# MasterControlChip.net
KiCad netlist of a schematic drawn in Altium Designer
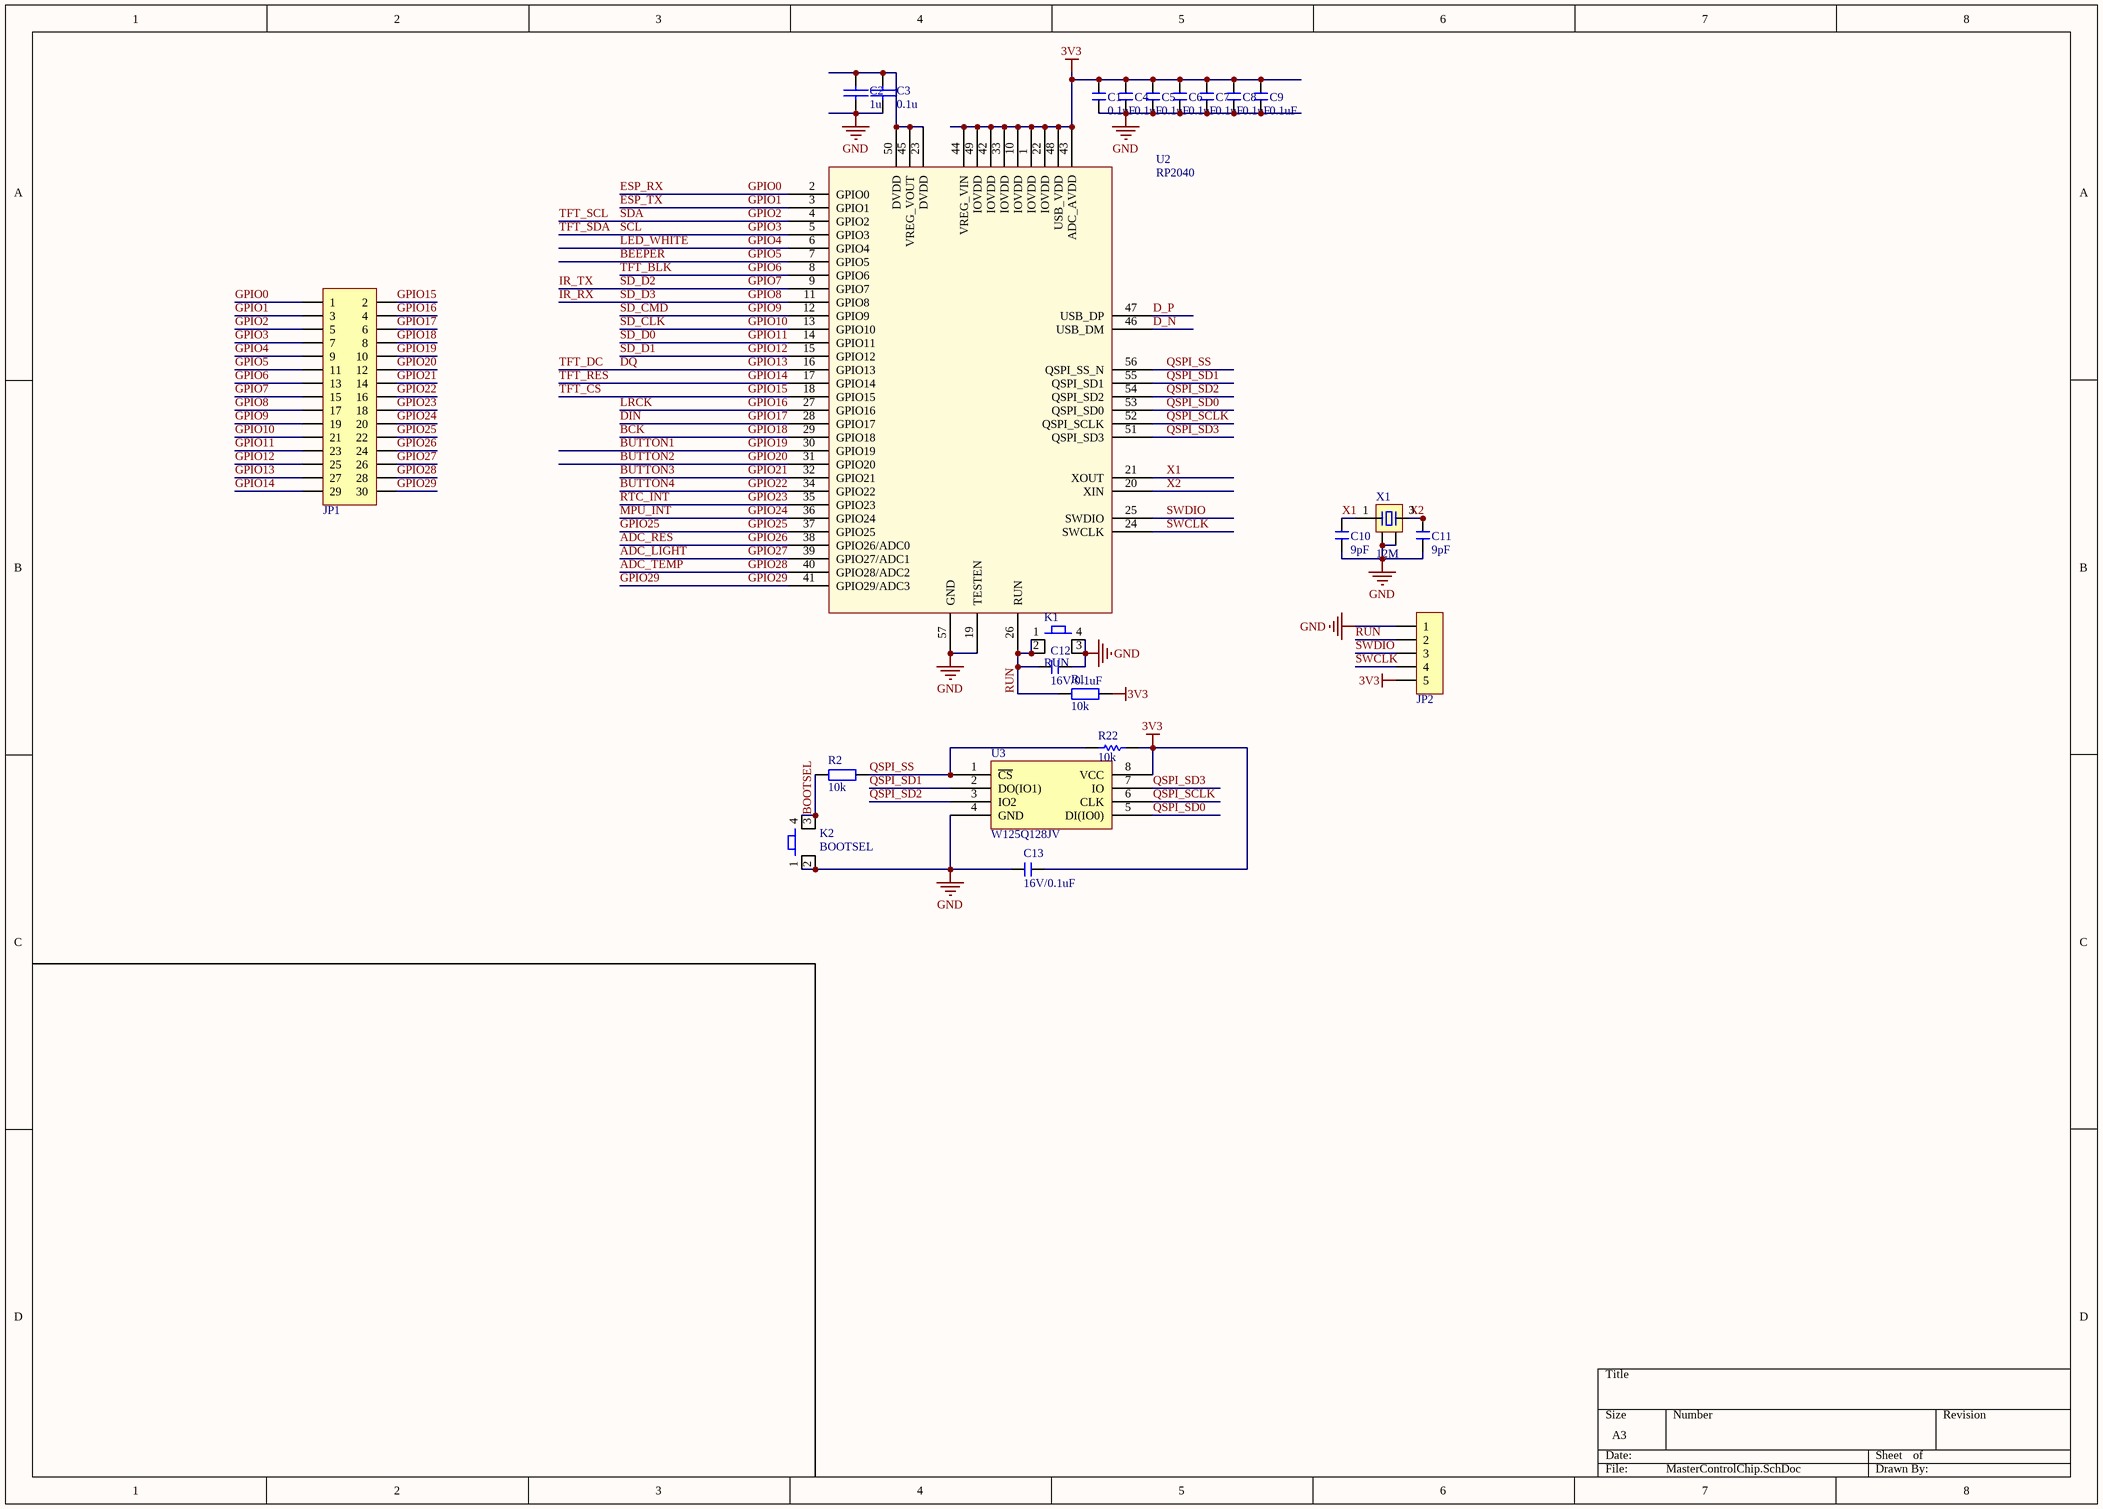
[diagram p0: MasterControlChip.SchDoc]

(export (version "E")
  (design (tool "Eeschema 10.0.6"))
  (components
    (comp (ref "C1")
      (value "0.1uF")
      (footprint "C 0603_L")
      (description "无极性贴片电容")
      (fields (field (name "版权归属") "源创客"))
      (libsource (lib "3.1   - 电阻-电容-电感") (part "C"))
    )
    (comp (ref "C2")
      (value "1u")
      (footprint "C 0603_L")
      (description "靠近RP2040")
      (libsource (lib "电容") (part "CAP"))
    )
    (comp (ref "C3")
      (value "0.1u")
      (footprint "C 0603_L")
      (description "无极性电容")
      (libsource (lib "电容") (part "CAP"))
    )
    (comp (ref "C4")
      (value "0.1uF")
      (footprint "C 0603_L")
      (description "无极性贴片电容")
      (fields (field (name "版权归属") "源创客"))
      (libsource (lib "3.1   - 电阻-电容-电感") (part "C"))
    )
    (comp (ref "C5")
      (value "0.1uF")
      (footprint "C 0603_L")
      (description "无极性贴片电容")
      (fields (field (name "版权归属") "源创客"))
      (libsource (lib "3.1   - 电阻-电容-电感") (part "C"))
    )
    (comp (ref "C6")
      (value "0.1uF")
      (footprint "C 0603_L")
      (description "无极性贴片电容")
      (fields (field (name "版权归属") "源创客"))
      (libsource (lib "3.1   - 电阻-电容-电感") (part "C"))
    )
    (comp (ref "C7")
      (value "0.1uF")
      (footprint "C 0603_L")
      (description "无极性贴片电容")
      (fields (field (name "版权归属") "源创客"))
      (libsource (lib "3.1   - 电阻-电容-电感") (part "C"))
    )
    (comp (ref "C8")
      (value "0.1uF")
      (footprint "C 0603_L")
      (description "无极性贴片电容")
      (fields (field (name "版权归属") "源创客"))
      (libsource (lib "3.1   - 电阻-电容-电感") (part "C"))
    )
    (comp (ref "C9")
      (value "0.1uF")
      (footprint "C 0603_L")
      (description "无极性贴片电容")
      (fields (field (name "版权归属") "源创客"))
      (libsource (lib "3.1   - 电阻-电容-电感") (part "C"))
    )
    (comp (ref "C10")
      (value "9pF")
      (footprint "C 0603_L")
      (description "无极性贴片电容")
      (fields (field (name "版权归属") "源创客"))
      (libsource (lib "3.1   - 电阻-电容-电感") (part "C"))
    )
    (comp (ref "C11")
      (value "9pF")
      (footprint "C 0603_L")
      (description "无极性贴片电容")
      (fields (field (name "版权归属") "源创客"))
      (libsource (lib "3.1   - 电阻-电容-电感") (part "C"))
    )
    (comp (ref "C12")
      (value "16V/0.1uF")
      (footprint "C 0603_L")
      (description "无极性贴片电容")
      (fields (field (name "版权归属") "源创客"))
      (libsource (lib "3.1   - 电阻-电容-电感") (part "C"))
    )
    (comp (ref "C13")
      (value "16V/0.1uF")
      (footprint "C 0603_L")
      (description "无极性贴片电容")
      (fields (field (name "版权归属") "源创客"))
      (libsource (lib "3.1   - 电阻-电容-电感") (part "C"))
    )
    (comp (ref "JP1")
      (value "Header 2X11")
      (footprint "HDR2.54-LI-2x15P")
      (description "15*2P接插件")
      (fields (field (name "版权归属") "源创客"))
      (libsource (lib "4.6   - 接插件-脚距2.54") (part "Header 15X2"))
    )
    (comp (ref "JP2")
      (value "HDR-1X5")
      (footprint "HDR2.54-M-LI-5P")
      (description "5P接插件")
      (fields (field (name "版权归属") "源创客"))
      (libsource (lib "4.6   - 接插件-脚距2.54") (part "Header 5"))
    )
    (comp (ref "K1") (value "RUN") (footprint "四角贴片开关") (libsource (lib "Schlib1") (part "四角轻触开关")))
    (comp (ref "K2") (value "BOOTSEL") (footprint "四角贴片开关") (libsource (lib "Schlib1") (part "四角轻触开关")))
    (comp (ref "R1")
      (value "10k")
      (footprint "R 0603_L")
      (description "贴片电阻")
      (fields (field (name "版权归属") "源创客"))
      (libsource (lib "3.1   - 电阻-电容-电感") (part "R"))
    )
    (comp (ref "R2")
      (value "10k")
      (footprint "R 0603_L")
      (description "贴片电阻")
      (fields (field (name "版权归属") "源创客"))
      (libsource (lib "3.1   - 电阻-电容-电感") (part "R"))
    )
    (comp (ref "R22") (value "10k") (footprint "0603R") (libsource (lib "电阻") (part "RES")))
    (comp (ref "U2") (value "RP2040") (footprint "QFN-56") (libsource (lib "Schlib1") (part "RP2040")))
    (comp (ref "U3")
      (value "W125Q128JV")
      (footprint "SOIC-8-208mil")
      (libsource (lib "Schlib1") (part "W125Q128JV"))
    )
    (comp (ref "X1")
      (value "12M")
      (footprint "OSC 3225-4P")
      (description "4脚无源晶振")
      (libsource (lib "晶振") (part "XTAL-4P"))
    )
  )
  (nets
    (net (code "1") (name "/ADC_LIGHT") (class "Default")
      (node (ref "JP1") (pin "26") (pinfunction "26_26") (pintype "passive"))
      (node (ref "U2") (pin "39") (pinfunction "GPIO27/ADC1_39") (pintype "passive"))
    )
    (net (code "2") (name "/ADC_RES") (class "Default")
      (node (ref "JP1") (pin "24") (pinfunction "24_24") (pintype "passive"))
      (node (ref "U2") (pin "38") (pinfunction "GPIO26/ADC0_38") (pintype "passive"))
    )
    (net (code "3") (name "/ADC_TEMP") (class "Default")
      (node (ref "JP1") (pin "28") (pinfunction "28_28") (pintype "passive"))
      (node (ref "U2") (pin "40") (pinfunction "GPIO28/ADC2_40") (pintype "passive"))
    )
    (net (code "4") (name "/BCK") (class "Default")
      (node (ref "JP1") (pin "8") (pinfunction "8_8") (pintype "passive"))
      (node (ref "U2") (pin "29") (pinfunction "GPIO18_29") (pintype "passive"))
    )
    (net (code "5") (name "/BEEPER") (class "Default")
      (node (ref "JP1") (pin "11") (pinfunction "11_11") (pintype "passive"))
      (node (ref "U2") (pin "7") (pinfunction "GPIO5_7") (pintype "passive"))
    )
    (net (code "6") (name "/BOOTSEL") (class "Default")
      (node (ref "K2") (pin "3") (pinfunction "4_3") (pintype "passive"))
      (node (ref "K2") (pin "4") (pinfunction "5_4") (pintype "passive"))
      (node (ref "R2") (pin "2") (pinfunction "2_2") (pintype "passive"))
    )
    (net (code "7") (name "/BUTTON1") (class "Default")
      (node (ref "JP1") (pin "10") (pinfunction "10_10") (pintype "passive"))
      (node (ref "U2") (pin "30") (pinfunction "GPIO19_30") (pintype "passive"))
    )
    (net (code "8") (name "/BUTTON2") (class "Default")
      (node (ref "JP1") (pin "12") (pinfunction "12_12") (pintype "passive"))
      (node (ref "U2") (pin "31") (pinfunction "GPIO20_31") (pintype "passive"))
    )
    (net (code "9") (name "/BUTTON3") (class "Default")
      (node (ref "JP1") (pin "14") (pinfunction "14_14") (pintype "passive"))
      (node (ref "U2") (pin "32") (pinfunction "GPIO21_32") (pintype "passive"))
    )
    (net (code "10") (name "/BUTTON4") (class "Default")
      (node (ref "JP1") (pin "16") (pinfunction "16_16") (pintype "passive"))
      (node (ref "U2") (pin "34") (pinfunction "GPIO22_34") (pintype "passive"))
    )
    (net (code "11") (name "/DIN") (class "Default")
      (node (ref "JP1") (pin "6") (pinfunction "6_6") (pintype "passive"))
      (node (ref "U2") (pin "28") (pinfunction "GPIO17_28") (pintype "passive"))
    )
    (net (code "12") (name "/DQ") (class "Default")
      (node (ref "JP1") (pin "27") (pinfunction "27_27") (pintype "passive"))
      (node (ref "U2") (pin "16") (pinfunction "GPIO13_16") (pintype "passive"))
    )
    (net (code "13") (name "/D_N") (class "Default")
      (node (ref "U2") (pin "46") (pinfunction "USB_DM_46") (pintype "passive"))
    )
    (net (code "14") (name "/D_P") (class "Default")
      (node (ref "U2") (pin "47") (pinfunction "USB_DP_47") (pintype "passive"))
    )
    (net (code "15") (name "/ESP_RX") (class "Default")
      (node (ref "JP1") (pin "1") (pinfunction "1_1") (pintype "passive"))
      (node (ref "U2") (pin "2") (pinfunction "GPIO0_2") (pintype "passive"))
    )
    (net (code "16") (name "/ESP_TX") (class "Default")
      (node (ref "JP1") (pin "3") (pinfunction "3_3") (pintype "passive"))
      (node (ref "U2") (pin "3") (pinfunction "GPIO1_3") (pintype "passive"))
    )
    (net (code "17") (name "/GPIO2") (class "Default")
      (node (ref "JP1") (pin "5") (pinfunction "5_5") (pintype "passive"))
      (node (ref "U2") (pin "4") (pinfunction "GPIO2_4") (pintype "passive"))
    )
    (net (code "18") (name "/GPIO3") (class "Default")
      (node (ref "JP1") (pin "7") (pinfunction "7_7") (pintype "passive"))
      (node (ref "U2") (pin "5") (pinfunction "GPIO3_5") (pintype "passive"))
    )
    (net (code "19") (name "/GPIO4") (class "Default")
      (node (ref "JP1") (pin "9") (pinfunction "9_9") (pintype "passive"))
      (node (ref "U2") (pin "6") (pinfunction "GPIO4_6") (pintype "passive"))
    )
    (net (code "20") (name "/GPIO6") (class "Default")
      (node (ref "JP1") (pin "13") (pinfunction "13_13") (pintype "passive"))
      (node (ref "U2") (pin "8") (pinfunction "GPIO6_8") (pintype "passive"))
    )
    (net (code "21") (name "/GPIO7") (class "Default")
      (node (ref "JP1") (pin "15") (pinfunction "15_15") (pintype "passive"))
      (node (ref "U2") (pin "9") (pinfunction "GPIO7_9") (pintype "passive"))
    )
    (net (code "22") (name "/GPIO8") (class "Default")
      (node (ref "JP1") (pin "17") (pinfunction "17_17") (pintype "passive"))
      (node (ref "U2") (pin "11") (pinfunction "GPIO8_11") (pintype "passive"))
    )
    (net (code "23") (name "/GPIO9") (class "Default")
      (node (ref "JP1") (pin "19") (pinfunction "19_19") (pintype "passive"))
      (node (ref "U2") (pin "12") (pinfunction "GPIO9_12") (pintype "passive"))
    )
    (net (code "24") (name "/GPIO10") (class "Default")
      (node (ref "JP1") (pin "21") (pinfunction "21_21") (pintype "passive"))
      (node (ref "U2") (pin "13") (pinfunction "GPIO10_13") (pintype "passive"))
    )
    (net (code "25") (name "/GPIO11") (class "Default")
      (node (ref "JP1") (pin "23") (pinfunction "23_23") (pintype "passive"))
      (node (ref "U2") (pin "14") (pinfunction "GPIO11_14") (pintype "passive"))
    )
    (net (code "26") (name "/GPIO12") (class "Default")
      (node (ref "JP1") (pin "25") (pinfunction "25_25") (pintype "passive"))
      (node (ref "U2") (pin "15") (pinfunction "GPIO12_15") (pintype "passive"))
    )
    (net (code "27") (name "/GPIO14") (class "Default")
      (node (ref "JP1") (pin "29") (pinfunction "29_29") (pintype "passive"))
      (node (ref "U2") (pin "17") (pinfunction "GPIO14_17") (pintype "passive"))
    )
    (net (code "28") (name "/GPIO15") (class "Default")
      (node (ref "JP1") (pin "2") (pinfunction "2_2") (pintype "passive"))
      (node (ref "U2") (pin "18") (pinfunction "GPIO15_18") (pintype "passive"))
    )
    (net (code "29") (name "/GPIO16") (class "Default")
      (node (ref "JP1") (pin "4") (pinfunction "4_4") (pintype "passive"))
      (node (ref "U2") (pin "27") (pinfunction "GPIO16_27") (pintype "passive"))
    )
    (net (code "30") (name "/GPIO23") (class "Default")
      (node (ref "JP1") (pin "18") (pinfunction "18_18") (pintype "passive"))
      (node (ref "U2") (pin "35") (pinfunction "GPIO23_35") (pintype "passive"))
    )
    (net (code "31") (name "/GPIO24") (class "Default")
      (node (ref "JP1") (pin "20") (pinfunction "20_20") (pintype "passive"))
      (node (ref "U2") (pin "36") (pinfunction "GPIO24_36") (pintype "passive"))
    )
    (net (code "32") (name "/GPIO25") (class "Default")
      (node (ref "JP1") (pin "22") (pinfunction "22_22") (pintype "passive"))
      (node (ref "U2") (pin "37") (pinfunction "GPIO25_37") (pintype "passive"))
    )
    (net (code "33") (name "/GPIO29") (class "Default")
      (node (ref "JP1") (pin "30") (pinfunction "30_30") (pintype "passive"))
      (node (ref "U2") (pin "41") (pinfunction "GPIO29/ADC3_41") (pintype "passive"))
    )
    (net (code "34") (name "/QSPI_SCLK") (class "Default")
      (node (ref "U2") (pin "52") (pinfunction "QSPI_SCLK_52") (pintype "passive"))
      (node (ref "U3") (pin "6") (pinfunction "CLK_6") (pintype "passive"))
    )
    (net (code "35") (name "/QSPI_SD0") (class "Default")
      (node (ref "U2") (pin "53") (pinfunction "QSPI_SD0_53") (pintype "passive"))
      (node (ref "U3") (pin "5") (pinfunction "DI(IO0)_5") (pintype "passive"))
    )
    (net (code "36") (name "/QSPI_SD1") (class "Default")
      (node (ref "U2") (pin "55") (pinfunction "QSPI_SD1_55") (pintype "passive"))
      (node (ref "U3") (pin "2") (pinfunction "DO(IO1)_2") (pintype "passive"))
    )
    (net (code "37") (name "/QSPI_SD2") (class "Default")
      (node (ref "U2") (pin "54") (pinfunction "QSPI_SD2_54") (pintype "passive"))
      (node (ref "U3") (pin "3") (pinfunction "IO2_3") (pintype "passive"))
    )
    (net (code "38") (name "/QSPI_SD3") (class "Default")
      (node (ref "U2") (pin "51") (pinfunction "QSPI_SD3_51") (pintype "passive"))
      (node (ref "U3") (pin "7") (pinfunction "IO_7") (pintype "passive"))
    )
    (net (code "39") (name "/QSPI_SS") (class "Default")
      (node (ref "R2") (pin "1") (pinfunction "1_1") (pintype "passive"))
      (node (ref "R22") (pin "1") (pinfunction "1_1") (pintype "passive"))
      (node (ref "U2") (pin "56") (pinfunction "QSPI_SS_N_56") (pintype "passive"))
      (node (ref "U3") (pin "1") (pinfunction "~{CS}_1") (pintype "passive"))
    )
    (net (code "40") (name "/RUN") (class "Default")
      (node (ref "C12") (pin "2") (pinfunction "2_2") (pintype "passive"))
      (node (ref "JP2") (pin "2") (pinfunction "2_2") (pintype "passive"))
      (node (ref "K1") (pin "1") (pinfunction "2_1") (pintype "passive"))
      (node (ref "K1") (pin "2") (pinfunction "3_2") (pintype "passive"))
      (node (ref "R1") (pin "2") (pinfunction "2_2") (pintype "passive"))
      (node (ref "U2") (pin "26") (pinfunction "RUN_26") (pintype "passive"))
    )
    (net (code "41") (name "/SWCLK") (class "Default")
      (node (ref "JP2") (pin "4") (pinfunction "4_4") (pintype "passive"))
      (node (ref "U2") (pin "24") (pinfunction "SWCLK_24") (pintype "passive"))
    )
    (net (code "42") (name "/SWDIO") (class "Default")
      (node (ref "JP2") (pin "3") (pinfunction "3_3") (pintype "passive"))
      (node (ref "U2") (pin "25") (pinfunction "SWDIO_25") (pintype "passive"))
    )
    (net (code "43") (name "/X1") (class "Default")
      (node (ref "C10") (pin "2") (pinfunction "2_2") (pintype "passive"))
      (node (ref "U2") (pin "21") (pinfunction "XOUT_21") (pintype "passive"))
      (node (ref "X1") (pin "1") (pinfunction "1_1") (pintype "passive"))
    )
    (net (code "44") (name "/X2") (class "Default")
      (node (ref "C11") (pin "2") (pinfunction "2_2") (pintype "passive"))
      (node (ref "U2") (pin "20") (pinfunction "XIN_20") (pintype "passive"))
      (node (ref "X1") (pin "3") (pinfunction "3_3") (pintype "passive"))
    )
    (net (code "45") (name "3V3") (class "Default")
      (node (ref "C1") (pin "2") (pinfunction "2_2") (pintype "passive"))
      (node (ref "C13") (pin "1") (pinfunction "1_1") (pintype "passive"))
      (node (ref "C4") (pin "2") (pinfunction "2_2") (pintype "passive"))
      (node (ref "C5") (pin "2") (pinfunction "2_2") (pintype "passive"))
      (node (ref "C6") (pin "2") (pinfunction "2_2") (pintype "passive"))
      (node (ref "C7") (pin "2") (pinfunction "2_2") (pintype "passive"))
      (node (ref "C8") (pin "2") (pinfunction "2_2") (pintype "passive"))
      (node (ref "C9") (pin "2") (pinfunction "2_2") (pintype "passive"))
      (node (ref "JP2") (pin "5") (pinfunction "5_5") (pintype "passive"))
      (node (ref "R1") (pin "1") (pinfunction "1_1") (pintype "passive"))
      (node (ref "R22") (pin "2") (pinfunction "2_2") (pintype "passive"))
      (node (ref "U2") (pin "1") (pinfunction "IOVDD_1") (pintype "passive"))
      (node (ref "U2") (pin "10") (pinfunction "IOVDD_10") (pintype "passive"))
      (node (ref "U2") (pin "22") (pinfunction "IOVDD_22") (pintype "passive"))
      (node (ref "U2") (pin "33") (pinfunction "IOVDD_33") (pintype "passive"))
      (node (ref "U2") (pin "42") (pinfunction "IOVDD_42") (pintype "passive"))
      (node (ref "U2") (pin "43") (pinfunction "ADC_AVDD_43") (pintype "passive"))
      (node (ref "U2") (pin "44") (pinfunction "VREG_VIN_44") (pintype "passive"))
      (node (ref "U2") (pin "48") (pinfunction "USB_VDD_48") (pintype "passive"))
      (node (ref "U2") (pin "49") (pinfunction "IOVDD_49") (pintype "passive"))
      (node (ref "U3") (pin "8") (pinfunction "VCC_8") (pintype "power_in"))
    )
    (net (code "46") (name "GND") (class "Default")
      (node (ref "C1") (pin "1") (pinfunction "1_1") (pintype "passive"))
      (node (ref "C10") (pin "1") (pinfunction "1_1") (pintype "passive"))
      (node (ref "C11") (pin "1") (pinfunction "1_1") (pintype "passive"))
      (node (ref "C12") (pin "1") (pinfunction "1_1") (pintype "passive"))
      (node (ref "C13") (pin "2") (pinfunction "2_2") (pintype "passive"))
      (node (ref "C2") (pin "1") (pinfunction "1_1") (pintype "passive"))
      (node (ref "C3") (pin "1") (pinfunction "1_1") (pintype "passive"))
      (node (ref "C4") (pin "1") (pinfunction "1_1") (pintype "passive"))
      (node (ref "C5") (pin "1") (pinfunction "1_1") (pintype "passive"))
      (node (ref "C6") (pin "1") (pinfunction "1_1") (pintype "passive"))
      (node (ref "C7") (pin "1") (pinfunction "1_1") (pintype "passive"))
      (node (ref "C8") (pin "1") (pinfunction "1_1") (pintype "passive"))
      (node (ref "C9") (pin "1") (pinfunction "1_1") (pintype "passive"))
      (node (ref "JP2") (pin "1") (pinfunction "1_1") (pintype "passive"))
      (node (ref "K1") (pin "3") (pinfunction "4_3") (pintype "passive"))
      (node (ref "K1") (pin "4") (pinfunction "5_4") (pintype "passive"))
      (node (ref "K2") (pin "1") (pinfunction "2_1") (pintype "passive"))
      (node (ref "K2") (pin "2") (pinfunction "3_2") (pintype "passive"))
      (node (ref "U2") (pin "19") (pinfunction "TESTEN_19") (pintype "passive"))
      (node (ref "U2") (pin "57") (pinfunction "GND_57") (pintype "passive"))
      (node (ref "U3") (pin "4") (pinfunction "GND_4") (pintype "power_in"))
      (node (ref "X1") (pin "2") (pinfunction "2_2") (pintype "passive"))
      (node (ref "X1") (pin "4") (pinfunction "4_4") (pintype "passive"))
    )
    (net (code "47") (name "Net-(U2-VREG_VOUT)") (class "Default")
      (node (ref "C2") (pin "2") (pinfunction "2_2") (pintype "passive"))
      (node (ref "C3") (pin "2") (pinfunction "2_2") (pintype "passive"))
      (node (ref "U2") (pin "23") (pinfunction "DVDD_23") (pintype "passive"))
      (node (ref "U2") (pin "45") (pinfunction "VREG_VOUT_45") (pintype "passive"))
      (node (ref "U2") (pin "50") (pinfunction "DVDD_50") (pintype "passive"))
    )
  )
)
